# 02-RCB_Header.net
KiCad netlist of a schematic drawn in Altium Designer
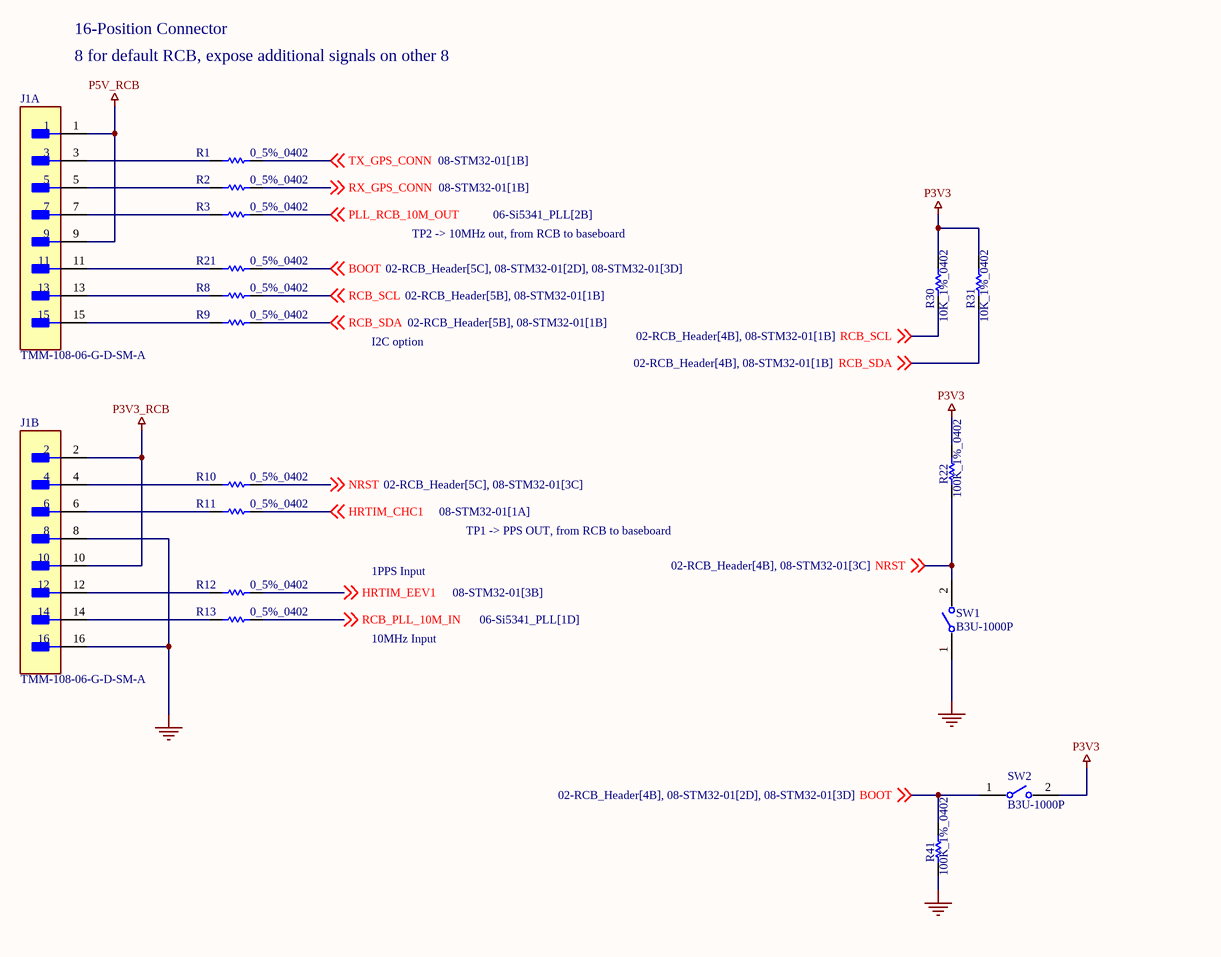
[diagram p0: 02-RCB_Header.SchDoc]

(export (version "E")
  (design (tool "Eeschema 10.0.6"))
  (components
    (comp (ref "J1")
      (value "TMM-108-06-G-D-SM-A")
      (footprint "FP-TMM-108-06-G-D-SM-A-MFG")
      (description "CONN HEADER SMD 16POS 2MM")
      (libsource (lib "Altium Content Vault") (part "4b6d22b45e2f925f038cba5d936fbcc"))
    )
    (comp (ref "R1")
      (value "0_5%_0402")
      (footprint "RESC1005X40X25NL05T10")
      (fields (field (name "MANUFACTURER") "Panasonic") (field (name "PART NUMBER") "ERJ-U020R00X"))
      (libsource (lib "Altium Content Vault") (part "RES"))
    )
    (comp (ref "R2")
      (value "0_5%_0402")
      (footprint "RESC1005X40X25NL05T10")
      (fields (field (name "MANUFACTURER") "Panasonic") (field (name "PART NUMBER") "ERJ-U020R00X"))
      (libsource (lib "Altium Content Vault") (part "RES"))
    )
    (comp (ref "R3")
      (value "0_5%_0402")
      (footprint "RESC1005X40X25NL05T10")
      (fields (field (name "MANUFACTURER") "Panasonic") (field (name "PART NUMBER") "ERJ-U020R00X"))
      (libsource (lib "Altium Content Vault") (part "RES"))
    )
    (comp (ref "R8")
      (value "0_5%_0402")
      (footprint "RESC1005X40X25NL05T10")
      (fields (field (name "MANUFACTURER") "Panasonic") (field (name "PART NUMBER") "ERJ-U020R00X"))
      (libsource (lib "Altium Content Vault") (part "RES"))
    )
    (comp (ref "R9")
      (value "0_5%_0402")
      (footprint "RESC1005X40X25NL05T10")
      (fields (field (name "MANUFACTURER") "Panasonic") (field (name "PART NUMBER") "ERJ-U020R00X"))
      (libsource (lib "Altium Content Vault") (part "RES"))
    )
    (comp (ref "R10")
      (value "0_5%_0402")
      (footprint "RESC1005X40X25NL05T10")
      (fields (field (name "MANUFACTURER") "Panasonic") (field (name "PART NUMBER") "ERJ-U020R00X"))
      (libsource (lib "Altium Content Vault") (part "RES"))
    )
    (comp (ref "R11")
      (value "0_5%_0402")
      (footprint "RESC1005X40X25NL05T10")
      (fields (field (name "MANUFACTURER") "Panasonic") (field (name "PART NUMBER") "ERJ-U020R00X"))
      (libsource (lib "Altium Content Vault") (part "RES"))
    )
    (comp (ref "R12")
      (value "0_5%_0402")
      (footprint "RESC1005X40X25NL05T10")
      (fields (field (name "MANUFACTURER") "Panasonic") (field (name "PART NUMBER") "ERJ-U020R00X"))
      (libsource (lib "Altium Content Vault") (part "RES"))
    )
    (comp (ref "R13")
      (value "0_5%_0402")
      (footprint "RESC1005X40X25NL05T10")
      (fields (field (name "MANUFACTURER") "Panasonic") (field (name "PART NUMBER") "ERJ-U020R00X"))
      (libsource (lib "Altium Content Vault") (part "RES"))
    )
    (comp (ref "R21")
      (value "0_5%_0402")
      (footprint "RESC1005X40X25NL05T10")
      (fields (field (name "MANUFACTURER") "Panasonic") (field (name "PART NUMBER") "ERJ-U020R00X"))
      (libsource (lib "Altium Content Vault") (part "RES"))
    )
    (comp (ref "R22")
      (value "100K_1%_0402")
      (footprint "RESC1005X40X25ML05T10")
      (fields (field (name "MANUFACTURER") "Yageo") (field (name "PART NUMBER") "RC0402FR-13100KL"))
      (libsource (lib "Altium Content Vault") (part "RES"))
    )
    (comp (ref "R30")
      (value "10K_1%_0402")
      (footprint "RESC1005X40X25NL10T10")
      (fields (field (name "MANUFACTURER") "Bourns") (field (name "PART NUMBER") "CR0402-FX-1002GLF"))
      (libsource (lib "Altium Content Vault") (part "RES"))
    )
    (comp (ref "R31")
      (value "10K_1%_0402")
      (footprint "RESC1005X40X25NL10T10")
      (fields (field (name "MANUFACTURER") "Bourns") (field (name "PART NUMBER") "CR0402-FX-1002GLF"))
      (libsource (lib "Altium Content Vault") (part "RES"))
    )
    (comp (ref "R41")
      (value "100K_1%_0402")
      (footprint "RESC1005X40X25ML05T10")
      (fields (field (name "MANUFACTURER") "Yageo") (field (name "PART NUMBER") "RC0402FR-13100KL"))
      (libsource (lib "Altium Content Vault") (part "RES"))
    )
    (comp (ref "SW1")
      (value "B3U-1000P")
      (footprint "FP-B3U-1000P-MFG")
      (description "SWITCH TACTILE SPST-NO 0.05A 12V")
      (libsource (lib "Altium Content Vault") (part "ae622034201233ca1abcedc05908f33"))
    )
    (comp (ref "SW2")
      (value "B3U-1000P")
      (footprint "FP-B3U-1000P-MFG")
      (description "SWITCH TACTILE SPST-NO 0.05A 12V")
      (libsource (lib "Altium Content Vault") (part "ae622034201233ca1abcedc05908f33"))
    )
  )
  (nets
    (net (code "1") (name "BOOT") (class "Default")
      (node (ref "R21") (pin "2") (pinfunction "2_2") (pintype "passive"))
      (node (ref "R41") (pin "2") (pinfunction "2_2") (pintype "passive"))
      (node (ref "SW2") (pin "1") (pinfunction "1_1") (pintype "passive"))
    )
    (net (code "2") (name "GND") (class "Default")
      (node (ref "J1") (pin "16") (pinfunction "16_16") (pintype "passive"))
      (node (ref "J1") (pin "8") (pinfunction "8_8") (pintype "passive"))
      (node (ref "R41") (pin "1") (pinfunction "1_1") (pintype "passive"))
      (node (ref "SW1") (pin "1") (pinfunction "1_1") (pintype "passive"))
    )
    (net (code "3") (name "HRTIM_CHC1") (class "Default")
      (node (ref "R11") (pin "2") (pinfunction "2_2") (pintype "passive"))
    )
    (net (code "4") (name "HRTIM_EEV1") (class "Default")
      (node (ref "R12") (pin "2") (pinfunction "2_2") (pintype "passive"))
    )
    (net (code "5") (name "NRST") (class "Default")
      (node (ref "R10") (pin "2") (pinfunction "2_2") (pintype "passive"))
      (node (ref "R22") (pin "1") (pinfunction "1_1") (pintype "passive"))
      (node (ref "SW1") (pin "2") (pinfunction "2_2") (pintype "passive"))
    )
    (net (code "6") (name "Net-(J1-Pad3)") (class "Default")
      (node (ref "J1") (pin "3") (pinfunction "3_3") (pintype "passive"))
      (node (ref "R1") (pin "1") (pinfunction "1_1") (pintype "passive"))
    )
    (net (code "7") (name "Net-(J1-Pad4)") (class "Default")
      (node (ref "J1") (pin "4") (pinfunction "4_4") (pintype "passive"))
      (node (ref "R10") (pin "1") (pinfunction "1_1") (pintype "passive"))
    )
    (net (code "8") (name "Net-(J1-Pad5)") (class "Default")
      (node (ref "J1") (pin "5") (pinfunction "5_5") (pintype "passive"))
      (node (ref "R2") (pin "1") (pinfunction "1_1") (pintype "passive"))
    )
    (net (code "9") (name "Net-(J1-Pad6)") (class "Default")
      (node (ref "J1") (pin "6") (pinfunction "6_6") (pintype "passive"))
      (node (ref "R11") (pin "1") (pinfunction "1_1") (pintype "passive"))
    )
    (net (code "10") (name "Net-(J1-Pad7)") (class "Default")
      (node (ref "J1") (pin "7") (pinfunction "7_7") (pintype "passive"))
      (node (ref "R3") (pin "1") (pinfunction "1_1") (pintype "passive"))
    )
    (net (code "11") (name "Net-(J1-Pad11)") (class "Default")
      (node (ref "J1") (pin "11") (pinfunction "11_11") (pintype "passive"))
      (node (ref "R21") (pin "1") (pinfunction "1_1") (pintype "passive"))
    )
    (net (code "12") (name "Net-(J1-Pad12)") (class "Default")
      (node (ref "J1") (pin "12") (pinfunction "12_12") (pintype "passive"))
      (node (ref "R12") (pin "1") (pinfunction "1_1") (pintype "passive"))
    )
    (net (code "13") (name "Net-(J1-Pad13)") (class "Default")
      (node (ref "J1") (pin "13") (pinfunction "13_13") (pintype "passive"))
      (node (ref "R8") (pin "1") (pinfunction "1_1") (pintype "passive"))
    )
    (net (code "14") (name "Net-(J1-Pad14)") (class "Default")
      (node (ref "J1") (pin "14") (pinfunction "14_14") (pintype "passive"))
      (node (ref "R13") (pin "1") (pinfunction "1_1") (pintype "passive"))
    )
    (net (code "15") (name "Net-(J1-Pad15)") (class "Default")
      (node (ref "J1") (pin "15") (pinfunction "15_15") (pintype "passive"))
      (node (ref "R9") (pin "1") (pinfunction "1_1") (pintype "passive"))
    )
    (net (code "16") (name "P3V3") (class "Default")
      (node (ref "R22") (pin "2") (pinfunction "2_2") (pintype "passive"))
      (node (ref "R30") (pin "2") (pinfunction "2_2") (pintype "passive"))
      (node (ref "R31") (pin "2") (pinfunction "2_2") (pintype "passive"))
      (node (ref "SW2") (pin "2") (pinfunction "2_2") (pintype "passive"))
    )
    (net (code "17") (name "P3V3_RCB") (class "Default")
      (node (ref "J1") (pin "10") (pinfunction "10_10") (pintype "passive"))
      (node (ref "J1") (pin "2") (pinfunction "2_2") (pintype "passive"))
    )
    (net (code "18") (name "P5V_RCB") (class "Default")
      (node (ref "J1") (pin "1") (pinfunction "1_1") (pintype "passive"))
      (node (ref "J1") (pin "9") (pinfunction "9_9") (pintype "passive"))
    )
    (net (code "19") (name "PLL_RCB_10M_OUT") (class "Default")
      (node (ref "R3") (pin "2") (pinfunction "2_2") (pintype "passive"))
    )
    (net (code "20") (name "RCB_PLL_10M_IN") (class "Default")
      (node (ref "R13") (pin "2") (pinfunction "2_2") (pintype "passive"))
    )
    (net (code "21") (name "RCB_SCL") (class "Default")
      (node (ref "R30") (pin "1") (pinfunction "1_1") (pintype "passive"))
      (node (ref "R8") (pin "2") (pinfunction "2_2") (pintype "passive"))
    )
    (net (code "22") (name "RCB_SDA") (class "Default")
      (node (ref "R31") (pin "1") (pinfunction "1_1") (pintype "passive"))
      (node (ref "R9") (pin "2") (pinfunction "2_2") (pintype "passive"))
    )
    (net (code "23") (name "RX_GPS_CONN") (class "Default")
      (node (ref "R2") (pin "2") (pinfunction "2_2") (pintype "passive"))
    )
    (net (code "24") (name "TX_GPS_CONN") (class "Default")
      (node (ref "R1") (pin "2") (pinfunction "2_2") (pintype "passive"))
    )
  )
)
